# 6_Oscillator.net
KiCad netlist of a schematic drawn in Altium Designer
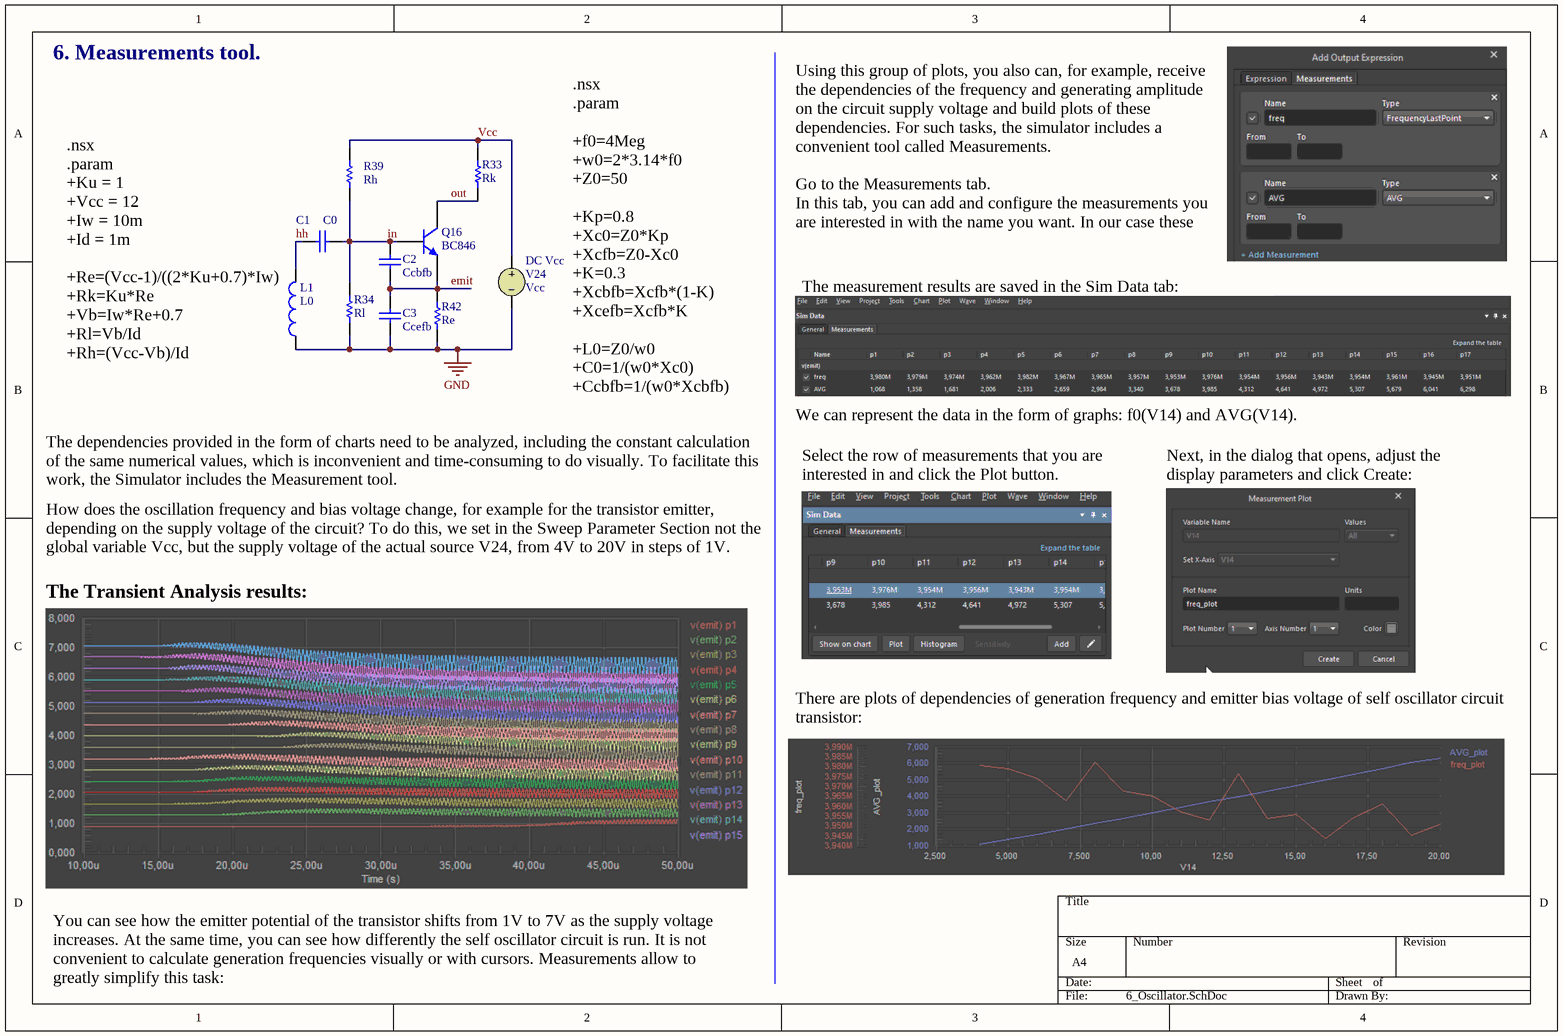
[diagram p0: 6_Oscillator.SchDoc]

(export (version "E")
  (design (tool "Eeschema 10.0.6"))
  (components
    (comp (ref "C1")
      (value "C0")
      (description "Capacitor")
      (libsource (lib "Simulation Generic Components") (part "Capacitor"))
    )
    (comp (ref "C2")
      (value "Ccbfb")
      (description "Capacitor")
      (libsource (lib "Simulation Generic Components") (part "Capacitor"))
    )
    (comp (ref "C3")
      (value "Ccefb")
      (description "Capacitor")
      (libsource (lib "Simulation Generic Components") (part "Capacitor"))
    )
    (comp (ref "L1")
      (value "L0")
      (description "Inductor")
      (libsource (lib "Simulation Generic Components") (part "Inductor"))
    )
    (comp (ref "Q16")
      (value "BC846")
      (footprint "TO-92A")
      (description "NPN General Purpose Amplifier")
      (fields (field (name "PUBLISHER") "Altium Limited"))
      (libsource (lib "Miscellaneous Devices") (part "2N3904"))
    )
    (comp (ref "R33")
      (value "Rk")
      (description "Resistor")
      (libsource (lib "Simulation Generic Components") (part "Resistor"))
    )
    (comp (ref "R34")
      (value "Rl")
      (description "Resistor")
      (libsource (lib "Simulation Generic Components") (part "Resistor"))
    )
    (comp (ref "R39")
      (value "Rh")
      (description "Resistor")
      (libsource (lib "Simulation Generic Components") (part "Resistor"))
    )
    (comp (ref "R42")
      (value "Re")
      (description "Resistor")
      (libsource (lib "Simulation Generic Components") (part "Resistor"))
    )
    (comp (ref "V24")
      (value "DC Vcc")
      (description "Voltage Source")
      (fields (field (name "ALTIUM_VALUE") "Vcc") (field (name "PUBLISHER") "Altium Limited"))
      (libsource (lib "Simulation Generic Components") (part "VSRC"))
    )
  )
  (nets
    (net (code "1") (name "/Vcc") (class "Default")
      (node (ref "R33") (pin "2") (pinfunction "2_2") (pintype "passive"))
      (node (ref "R39") (pin "2") (pinfunction "2_2") (pintype "passive"))
      (node (ref "V24") (pin "1") (pinfunction "1_1") (pintype "passive"))
    )
    (net (code "2") (name "/emit") (class "Default")
      (node (ref "C2") (pin "1") (pinfunction "1_1") (pintype "passive"))
      (node (ref "C3") (pin "2") (pinfunction "2_2") (pintype "passive"))
      (node (ref "Q16") (pin "1") (pinfunction "E_1") (pintype "passive"))
      (node (ref "R42") (pin "2") (pinfunction "2_2") (pintype "passive"))
    )
    (net (code "3") (name "/hh") (class "Default")
      (node (ref "C1") (pin "1") (pinfunction "1_1") (pintype "passive"))
      (node (ref "L1") (pin "2") (pinfunction "2_2") (pintype "passive"))
    )
    (net (code "4") (name "/in") (class "Default")
      (node (ref "C1") (pin "2") (pinfunction "2_2") (pintype "passive"))
      (node (ref "C2") (pin "2") (pinfunction "2_2") (pintype "passive"))
      (node (ref "Q16") (pin "2") (pinfunction "B_2") (pintype "passive"))
      (node (ref "R34") (pin "1") (pinfunction "1_1") (pintype "passive"))
      (node (ref "R39") (pin "1") (pinfunction "1_1") (pintype "passive"))
    )
    (net (code "5") (name "/out") (class "Default")
      (node (ref "Q16") (pin "3") (pinfunction "C_3") (pintype "passive"))
      (node (ref "R33") (pin "1") (pinfunction "1_1") (pintype "passive"))
    )
    (net (code "6") (name "GND") (class "Default")
      (node (ref "C3") (pin "1") (pinfunction "1_1") (pintype "passive"))
      (node (ref "L1") (pin "1") (pinfunction "1_1") (pintype "passive"))
      (node (ref "R34") (pin "2") (pinfunction "2_2") (pintype "passive"))
      (node (ref "R42") (pin "1") (pinfunction "1_1") (pintype "passive"))
      (node (ref "V24") (pin "2") (pinfunction "2_2") (pintype "passive"))
    )
  )
)
